# version_2_0.net
KiCad netlist of a schematic drawn in EAGLE
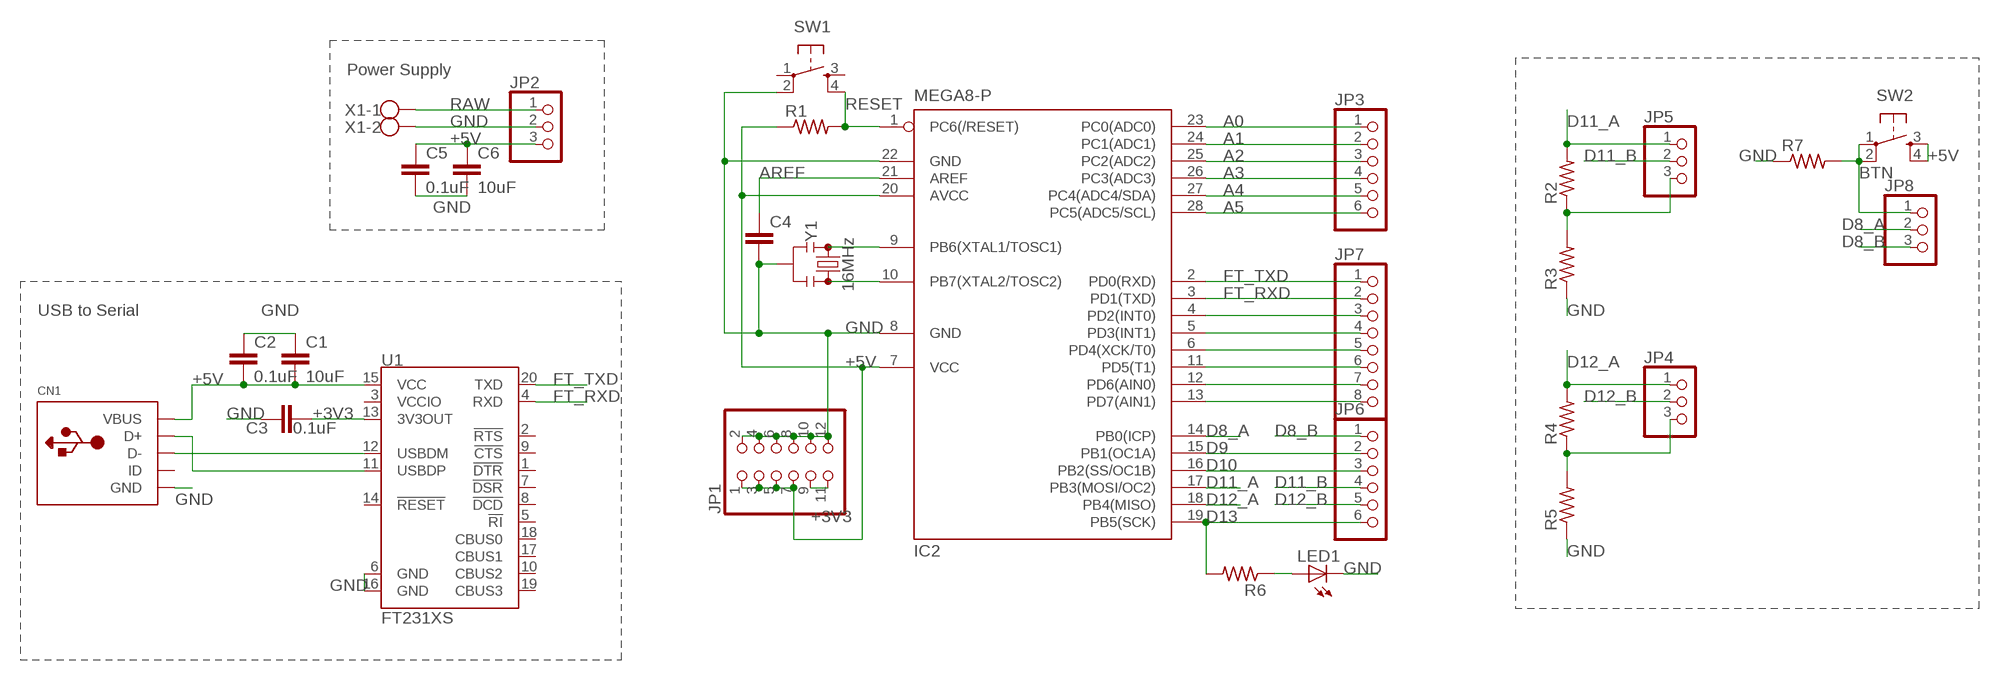
[diagram p0: schematic, sheet 1]

(export (version "E")
  (design (tool "Eeschema 10.0.6"))
  (components
    (comp (ref "C1")
      (value "10uF")
      (footprint "eagle-import:C0603")
      (libsource (lib "eagle-import") (part "C-EUC0603"))
    )
    (comp (ref "C2")
      (value "0.1uF")
      (footprint "eagle-import:C0603")
      (libsource (lib "eagle-import") (part "C-EUC0603"))
    )
    (comp (ref "C3")
      (value "0.1uF")
      (footprint "eagle-import:C0603")
      (libsource (lib "eagle-import") (part "C-EUC0603"))
    )
    (comp (ref "C4")
      (value "C-EUC0603")
      (footprint "eagle-import:C0603")
      (libsource (lib "eagle-import") (part "C-EUC0603"))
    )
    (comp (ref "C5")
      (value "0.1uF")
      (footprint "eagle-import:C0603")
      (libsource (lib "eagle-import") (part "C-EUC0603"))
    )
    (comp (ref "C6")
      (value "10uF")
      (footprint "eagle-import:C0603")
      (libsource (lib "eagle-import") (part "C-EUC0603"))
    )
    (comp (ref "CN1")
      (value "USBMINIB")
      (footprint "eagle-import:USB-MINIB")
      (libsource (lib "eagle-import") (part "USBMINIB"))
    )
    (comp (ref "IC2")
      (value "MEGA8-P")
      (footprint "eagle-import:DIL28-3")
      (libsource (lib "eagle-import") (part "MEGA8-P"))
    )
    (comp (ref "JP1")
      (value "PINHD-2X6")
      (footprint "eagle-import:2X06")
      (libsource (lib "eagle-import") (part "PINHD-2X6"))
    )
    (comp (ref "JP2")
      (value "PINHD-1X3")
      (footprint "eagle-import:1X03")
      (libsource (lib "eagle-import") (part "PINHD-1X3"))
    )
    (comp (ref "JP3")
      (value "PINHD-1X6")
      (footprint "eagle-import:1X06")
      (libsource (lib "eagle-import") (part "PINHD-1X6"))
    )
    (comp (ref "JP4")
      (value "PINHD-1X3")
      (footprint "eagle-import:1X03")
      (libsource (lib "eagle-import") (part "PINHD-1X3"))
    )
    (comp (ref "JP5")
      (value "PINHD-1X3")
      (footprint "eagle-import:1X03")
      (libsource (lib "eagle-import") (part "PINHD-1X3"))
    )
    (comp (ref "JP6")
      (value "PINHD-1X6")
      (footprint "eagle-import:1X06")
      (libsource (lib "eagle-import") (part "PINHD-1X6"))
    )
    (comp (ref "JP7")
      (value "PINHD-1X8")
      (footprint "eagle-import:1X08")
      (libsource (lib "eagle-import") (part "PINHD-1X8"))
    )
    (comp (ref "JP8")
      (value "PINHD-1X3")
      (footprint "eagle-import:1X03")
      (libsource (lib "eagle-import") (part "PINHD-1X3"))
    )
    (comp (ref "LED1")
      (value "LEDCHIP-LED0805")
      (footprint "eagle-import:CHIP-LED0805")
      (libsource (lib "eagle-import") (part "LEDCHIP-LED0805"))
    )
    (comp (ref "R1")
      (value "R-US_R0603")
      (footprint "eagle-import:R0603")
      (libsource (lib "eagle-import") (part "R-US_R0603"))
    )
    (comp (ref "R2")
      (value "R-US_R0603")
      (footprint "eagle-import:R0603")
      (libsource (lib "eagle-import") (part "R-US_R0603"))
    )
    (comp (ref "R3")
      (value "R-US_R0603")
      (footprint "eagle-import:R0603")
      (libsource (lib "eagle-import") (part "R-US_R0603"))
    )
    (comp (ref "R4")
      (value "R-US_R0603")
      (footprint "eagle-import:R0603")
      (libsource (lib "eagle-import") (part "R-US_R0603"))
    )
    (comp (ref "R5")
      (value "R-US_R0603")
      (footprint "eagle-import:R0603")
      (libsource (lib "eagle-import") (part "R-US_R0603"))
    )
    (comp (ref "R6")
      (value "R-US_R0603")
      (footprint "eagle-import:R0603")
      (libsource (lib "eagle-import") (part "R-US_R0603"))
    )
    (comp (ref "R7")
      (value "R-US_R0603")
      (footprint "eagle-import:R0603")
      (libsource (lib "eagle-import") (part "R-US_R0603"))
    )
    (comp (ref "SW1")
      (value "SWITCH_SPST_4_PINRECT")
      (footprint "eagle-import:TACTILE_SWITCH_SMD_4.6X2.8MM")
      (libsource (lib "eagle-import") (part "SWITCH_SPST_4_PINRECT"))
    )
    (comp (ref "SW2")
      (value "SWITCH_SPST_4_PINRECT")
      (footprint "eagle-import:TACTILE_SWITCH_SMD_4.6X2.8MM")
      (libsource (lib "eagle-import") (part "SWITCH_SPST_4_PINRECT"))
    )
    (comp (ref "U1")
      (value "FT231XS")
      (footprint "eagle-import:SSOP20_L")
      (libsource (lib "eagle-import") (part "FT231XS"))
    )
    (comp (ref "X1")
      (value "W237-102")
      (footprint "eagle-import:W237-102")
      (fields (field (name "MPN") "237-102"))
      (libsource (lib "eagle-import") (part "W237-102"))
    )
    (comp (ref "Y1")
      (value "16MHz")
      (footprint "eagle-import:RESONATOR-SMD-3.2X1.3")
      (libsource (lib "eagle-import") (part "RESONATOR-16MHZSMD_3.2X1.3"))
    )
  )
  (nets
    (net (code "1") (name "/+3V3") (class "Default")
      (node (ref "C3") (pin "2") (pinfunction "2_2") (pintype "passive"))
      (node (ref "JP1") (pin "11") (pinfunction "11_11") (pintype "passive"))
      (node (ref "JP1") (pin "9") (pinfunction "9_9") (pintype "passive"))
      (node (ref "U1") (pin "13") (pinfunction "3V3OUT_13") (pintype "bidirectional"))
    )
    (net (code "2") (name "/+5V") (class "Default")
      (node (ref "C1") (pin "2") (pinfunction "2_2") (pintype "passive"))
      (node (ref "C2") (pin "2") (pinfunction "2_2") (pintype "passive"))
      (node (ref "C5") (pin "1") (pinfunction "1_1") (pintype "passive"))
      (node (ref "C6") (pin "1") (pinfunction "1_1") (pintype "passive"))
      (node (ref "CN1") (pin "VBUS") (pinfunction "VBUS_VBUS") (pintype "power_in"))
      (node (ref "IC2") (pin "20") (pinfunction "AVCC_20") (pintype "power_in"))
      (node (ref "IC2") (pin "7") (pinfunction "VCC_7") (pintype "power_in"))
      (node (ref "JP1") (pin "1") (pinfunction "1_1") (pintype "passive"))
      (node (ref "JP1") (pin "3") (pinfunction "3_3") (pintype "passive"))
      (node (ref "JP1") (pin "5") (pinfunction "5_5") (pintype "passive"))
      (node (ref "JP1") (pin "7") (pinfunction "7_7") (pintype "passive"))
      (node (ref "JP2") (pin "3") (pinfunction "3_3") (pintype "passive"))
      (node (ref "R1") (pin "1") (pinfunction "1_1") (pintype "passive"))
      (node (ref "SW2") (pin "3") (pinfunction "3_3") (pintype "passive"))
      (node (ref "SW2") (pin "4") (pinfunction "4_4") (pintype "passive"))
      (node (ref "U1") (pin "15") (pinfunction "VCC_15") (pintype "bidirectional"))
    )
    (net (code "3") (name "/A0") (class "Default")
      (node (ref "IC2") (pin "23") (pinfunction "PC0(ADC0)_23") (pintype "bidirectional"))
      (node (ref "JP3") (pin "1") (pinfunction "1_1") (pintype "passive"))
    )
    (net (code "4") (name "/A1") (class "Default")
      (node (ref "IC2") (pin "24") (pinfunction "PC1(ADC1)_24") (pintype "bidirectional"))
      (node (ref "JP3") (pin "2") (pinfunction "2_2") (pintype "passive"))
    )
    (net (code "5") (name "/A2") (class "Default")
      (node (ref "IC2") (pin "25") (pinfunction "PC2(ADC2)_25") (pintype "bidirectional"))
      (node (ref "JP3") (pin "3") (pinfunction "3_3") (pintype "passive"))
    )
    (net (code "6") (name "/A3") (class "Default")
      (node (ref "IC2") (pin "26") (pinfunction "PC3(ADC3)_26") (pintype "bidirectional"))
      (node (ref "JP3") (pin "4") (pinfunction "4_4") (pintype "passive"))
    )
    (net (code "7") (name "/A4") (class "Default")
      (node (ref "IC2") (pin "27") (pinfunction "PC4(ADC4/SDA)_27") (pintype "bidirectional"))
      (node (ref "JP3") (pin "5") (pinfunction "5_5") (pintype "passive"))
    )
    (net (code "8") (name "/A5") (class "Default")
      (node (ref "IC2") (pin "28") (pinfunction "PC5(ADC5/SCL)_28") (pintype "bidirectional"))
      (node (ref "JP3") (pin "6") (pinfunction "6_6") (pintype "passive"))
    )
    (net (code "9") (name "/AREF") (class "Default")
      (node (ref "C4") (pin "1") (pinfunction "1_1") (pintype "passive"))
      (node (ref "IC2") (pin "21") (pinfunction "AREF_21") (pintype "passive"))
    )
    (net (code "10") (name "/BTN") (class "Default")
      (node (ref "JP8") (pin "1") (pinfunction "1_1") (pintype "passive"))
      (node (ref "R7") (pin "2") (pinfunction "2_2") (pintype "passive"))
      (node (ref "SW2") (pin "1") (pinfunction "1_1") (pintype "passive"))
      (node (ref "SW2") (pin "2") (pinfunction "2_2") (pintype "passive"))
    )
    (net (code "11") (name "/D8_A") (class "Default")
      (node (ref "IC2") (pin "14") (pinfunction "PB0(ICP)_14") (pintype "bidirectional"))
      (node (ref "JP8") (pin "2") (pinfunction "2_2") (pintype "passive"))
    )
    (net (code "12") (name "/D8_B") (class "Default")
      (node (ref "JP6") (pin "1") (pinfunction "1_1") (pintype "passive"))
      (node (ref "JP8") (pin "3") (pinfunction "3_3") (pintype "passive"))
    )
    (net (code "13") (name "/D9") (class "Default")
      (node (ref "IC2") (pin "15") (pinfunction "PB1(OC1A)_15") (pintype "bidirectional"))
      (node (ref "JP6") (pin "2") (pinfunction "2_2") (pintype "passive"))
    )
    (net (code "14") (name "/D10") (class "Default")
      (node (ref "IC2") (pin "16") (pinfunction "PB2(SS/OC1B)_16") (pintype "bidirectional"))
      (node (ref "JP6") (pin "3") (pinfunction "3_3") (pintype "passive"))
    )
    (net (code "15") (name "/D11_A") (class "Default")
      (node (ref "IC2") (pin "17") (pinfunction "PB3(MOSI/OC2)_17") (pintype "bidirectional"))
      (node (ref "JP5") (pin "1") (pinfunction "1_1") (pintype "passive"))
      (node (ref "R2") (pin "2") (pinfunction "2_2") (pintype "passive"))
    )
    (net (code "16") (name "/D11_B") (class "Default")
      (node (ref "JP5") (pin "2") (pinfunction "2_2") (pintype "passive"))
      (node (ref "JP6") (pin "4") (pinfunction "4_4") (pintype "passive"))
    )
    (net (code "17") (name "/D12_A") (class "Default")
      (node (ref "IC2") (pin "18") (pinfunction "PB4(MISO)_18") (pintype "bidirectional"))
      (node (ref "JP4") (pin "1") (pinfunction "1_1") (pintype "passive"))
      (node (ref "R4") (pin "2") (pinfunction "2_2") (pintype "passive"))
    )
    (net (code "18") (name "/D12_B") (class "Default")
      (node (ref "JP4") (pin "2") (pinfunction "2_2") (pintype "passive"))
      (node (ref "JP6") (pin "5") (pinfunction "5_5") (pintype "passive"))
    )
    (net (code "19") (name "/D13") (class "Default")
      (node (ref "IC2") (pin "19") (pinfunction "PB5(SCK)_19") (pintype "bidirectional"))
      (node (ref "JP6") (pin "6") (pinfunction "6_6") (pintype "passive"))
      (node (ref "R6") (pin "2") (pinfunction "2_2") (pintype "passive"))
    )
    (net (code "20") (name "/FT_RXD") (class "Default")
      (node (ref "IC2") (pin "3") (pinfunction "PD1(TXD)_3") (pintype "bidirectional"))
      (node (ref "JP7") (pin "2") (pinfunction "2_2") (pintype "passive"))
      (node (ref "U1") (pin "4") (pinfunction "RXD_4") (pintype "bidirectional"))
    )
    (net (code "21") (name "/FT_TXD") (class "Default")
      (node (ref "IC2") (pin "2") (pinfunction "PD0(RXD)_2") (pintype "bidirectional"))
      (node (ref "JP7") (pin "1") (pinfunction "1_1") (pintype "passive"))
      (node (ref "U1") (pin "20") (pinfunction "TXD_20") (pintype "bidirectional"))
    )
    (net (code "22") (name "/GND") (class "Default")
      (node (ref "C1") (pin "1") (pinfunction "1_1") (pintype "passive"))
      (node (ref "C2") (pin "1") (pinfunction "1_1") (pintype "passive"))
      (node (ref "C3") (pin "1") (pinfunction "1_1") (pintype "passive"))
      (node (ref "C4") (pin "2") (pinfunction "2_2") (pintype "passive"))
      (node (ref "C5") (pin "2") (pinfunction "2_2") (pintype "passive"))
      (node (ref "C6") (pin "2") (pinfunction "2_2") (pintype "passive"))
      (node (ref "CN1") (pin "GND") (pinfunction "GND_GND") (pintype "power_in"))
      (node (ref "IC2") (pin "22") (pinfunction "GND_22") (pintype "power_in"))
      (node (ref "IC2") (pin "8") (pinfunction "GND_8") (pintype "power_in"))
      (node (ref "JP1") (pin "10") (pinfunction "10_10") (pintype "passive"))
      (node (ref "JP1") (pin "12") (pinfunction "12_12") (pintype "passive"))
      (node (ref "JP1") (pin "2") (pinfunction "2_2") (pintype "passive"))
      (node (ref "JP1") (pin "4") (pinfunction "4_4") (pintype "passive"))
      (node (ref "JP1") (pin "6") (pinfunction "6_6") (pintype "passive"))
      (node (ref "JP1") (pin "8") (pinfunction "8_8") (pintype "passive"))
      (node (ref "JP2") (pin "2") (pinfunction "2_2") (pintype "passive"))
      (node (ref "LED1") (pin "C") (pinfunction "C_C") (pintype "passive"))
      (node (ref "R3") (pin "1") (pinfunction "1_1") (pintype "passive"))
      (node (ref "R5") (pin "1") (pinfunction "1_1") (pintype "passive"))
      (node (ref "R7") (pin "1") (pinfunction "1_1") (pintype "passive"))
      (node (ref "SW1") (pin "2") (pinfunction "2_2") (pintype "passive"))
      (node (ref "U1") (pin "16") (pinfunction "GND_16") (pintype "bidirectional"))
      (node (ref "U1") (pin "6") (pinfunction "GND_6") (pintype "bidirectional"))
      (node (ref "X1") (pin "2") (pinfunction "KL_2") (pintype "passive"))
      (node (ref "Y1") (pin "2") (pinfunction "2_2") (pintype "passive"))
    )
    (net (code "23") (name "/RAW") (class "Default")
      (node (ref "JP2") (pin "1") (pinfunction "1_1") (pintype "passive"))
      (node (ref "X1") (pin "1") (pinfunction "KL_1") (pintype "passive"))
    )
    (net (code "24") (name "/RESET") (class "Default")
      (node (ref "IC2") (pin "1") (pinfunction "PC6(/RESET)_1") (pintype "bidirectional"))
      (node (ref "R1") (pin "2") (pinfunction "2_2") (pintype "passive"))
      (node (ref "SW1") (pin "4") (pinfunction "4_4") (pintype "passive"))
    )
    (net (code "25") (name "Net-(IC2-PB6(XTAL1{slash}TOSC1))") (class "Default")
      (node (ref "IC2") (pin "9") (pinfunction "PB6(XTAL1/TOSC1)_9") (pintype "bidirectional"))
      (node (ref "Y1") (pin "1") (pinfunction "1_1") (pintype "passive"))
    )
    (net (code "26") (name "Net-(IC2-PB7(XTAL2{slash}TOSC2))") (class "Default")
      (node (ref "IC2") (pin "10") (pinfunction "PB7(XTAL2/TOSC2)_10") (pintype "bidirectional"))
      (node (ref "Y1") (pin "3") (pinfunction "3_3") (pintype "passive"))
    )
    (net (code "27") (name "Net-(IC2-PD2(INT0))") (class "Default")
      (node (ref "IC2") (pin "4") (pinfunction "PD2(INT0)_4") (pintype "bidirectional"))
      (node (ref "JP7") (pin "3") (pinfunction "3_3") (pintype "passive"))
    )
    (net (code "28") (name "Net-(IC2-PD3(INT1))") (class "Default")
      (node (ref "IC2") (pin "5") (pinfunction "PD3(INT1)_5") (pintype "bidirectional"))
      (node (ref "JP7") (pin "4") (pinfunction "4_4") (pintype "passive"))
    )
    (net (code "29") (name "Net-(IC2-PD4(XCK{slash}T0))") (class "Default")
      (node (ref "IC2") (pin "6") (pinfunction "PD4(XCK/T0)_6") (pintype "bidirectional"))
      (node (ref "JP7") (pin "5") (pinfunction "5_5") (pintype "passive"))
    )
    (net (code "30") (name "Net-(IC2-PD5(T1))") (class "Default")
      (node (ref "IC2") (pin "11") (pinfunction "PD5(T1)_11") (pintype "bidirectional"))
      (node (ref "JP7") (pin "6") (pinfunction "6_6") (pintype "passive"))
    )
    (net (code "31") (name "Net-(IC2-PD6(AIN0))") (class "Default")
      (node (ref "IC2") (pin "12") (pinfunction "PD6(AIN0)_12") (pintype "bidirectional"))
      (node (ref "JP7") (pin "7") (pinfunction "7_7") (pintype "passive"))
    )
    (net (code "32") (name "Net-(IC2-PD7(AIN1))") (class "Default")
      (node (ref "IC2") (pin "13") (pinfunction "PD7(AIN1)_13") (pintype "bidirectional"))
      (node (ref "JP7") (pin "8") (pinfunction "8_8") (pintype "passive"))
    )
    (net (code "33") (name "Net-(JP4-Pad3)") (class "Default")
      (node (ref "JP4") (pin "3") (pinfunction "3_3") (pintype "passive"))
      (node (ref "R4") (pin "1") (pinfunction "1_1") (pintype "passive"))
      (node (ref "R5") (pin "2") (pinfunction "2_2") (pintype "passive"))
    )
    (net (code "34") (name "Net-(JP5-Pad3)") (class "Default")
      (node (ref "JP5") (pin "3") (pinfunction "3_3") (pintype "passive"))
      (node (ref "R2") (pin "1") (pinfunction "1_1") (pintype "passive"))
      (node (ref "R3") (pin "2") (pinfunction "2_2") (pintype "passive"))
    )
    (net (code "35") (name "Net-(LED1-PadA)") (class "Default")
      (node (ref "LED1") (pin "A") (pinfunction "A_A") (pintype "passive"))
      (node (ref "R6") (pin "1") (pinfunction "1_1") (pintype "passive"))
    )
    (net (code "36") (name "Net-(U1-USBDM)") (class "Default")
      (node (ref "CN1") (pin "D-") (pinfunction "D-_D-") (pintype "bidirectional"))
      (node (ref "U1") (pin "12") (pinfunction "USBDM_12") (pintype "bidirectional"))
    )
    (net (code "37") (name "Net-(U1-USBDP)") (class "Default")
      (node (ref "CN1") (pin "D+") (pinfunction "D+_D+") (pintype "bidirectional"))
      (node (ref "U1") (pin "11") (pinfunction "USBDP_11") (pintype "bidirectional"))
    )
    (net (code "38") (name "unconnected-(CN1-PadID)") (class "Default")
      (node (ref "CN1") (pin "ID") (pinfunction "ID_ID") (pintype "bidirectional"))
    )
    (net (code "39") (name "unconnected-(SW1-Pad1)") (class "Default")
      (node (ref "SW1") (pin "1") (pinfunction "1_1") (pintype "passive"))
    )
    (net (code "40") (name "unconnected-(SW1-Pad3)") (class "Default")
      (node (ref "SW1") (pin "3") (pinfunction "3_3") (pintype "passive"))
    )
    (net (code "41") (name "unconnected-(U1-CBUS0-Pad18)") (class "Default")
      (node (ref "U1") (pin "18") (pinfunction "CBUS0_18") (pintype "bidirectional"))
    )
    (net (code "42") (name "unconnected-(U1-CBUS1-Pad17)") (class "Default")
      (node (ref "U1") (pin "17") (pinfunction "CBUS1_17") (pintype "bidirectional"))
    )
    (net (code "43") (name "unconnected-(U1-CBUS2-Pad10)") (class "Default")
      (node (ref "U1") (pin "10") (pinfunction "CBUS2_10") (pintype "bidirectional"))
    )
    (net (code "44") (name "unconnected-(U1-CBUS3-Pad19)") (class "Default")
      (node (ref "U1") (pin "19") (pinfunction "CBUS3_19") (pintype "bidirectional"))
    )
    (net (code "45") (name "unconnected-(U1-VCCIO-Pad3)") (class "Default")
      (node (ref "U1") (pin "3") (pinfunction "VCCIO_3") (pintype "bidirectional"))
    )
    (net (code "46") (name "unconnected-(U1-~{CTS}-Pad9)") (class "Default")
      (node (ref "U1") (pin "9") (pinfunction "~{CTS}_9") (pintype "bidirectional"))
    )
    (net (code "47") (name "unconnected-(U1-~{DCD}-Pad8)") (class "Default")
      (node (ref "U1") (pin "8") (pinfunction "~{DCD}_8") (pintype "bidirectional"))
    )
    (net (code "48") (name "unconnected-(U1-~{DSR}-Pad7)") (class "Default")
      (node (ref "U1") (pin "7") (pinfunction "~{DSR}_7") (pintype "bidirectional"))
    )
    (net (code "49") (name "unconnected-(U1-~{DTR}-Pad1)") (class "Default")
      (node (ref "U1") (pin "1") (pinfunction "~{DTR}_1") (pintype "bidirectional"))
    )
    (net (code "50") (name "unconnected-(U1-~{RESET}-Pad14)") (class "Default")
      (node (ref "U1") (pin "14") (pinfunction "~{RESET}_14") (pintype "bidirectional"))
    )
    (net (code "51") (name "unconnected-(U1-~{RI}-Pad5)") (class "Default")
      (node (ref "U1") (pin "5") (pinfunction "~{RI}_5") (pintype "bidirectional"))
    )
    (net (code "52") (name "unconnected-(U1-~{RTS}-Pad2)") (class "Default")
      (node (ref "U1") (pin "2") (pinfunction "~{RTS}_2") (pintype "bidirectional"))
    )
  )
)
